# P0_Main_Connect.net
KiCad netlist of a schematic drawn in Altium Designer
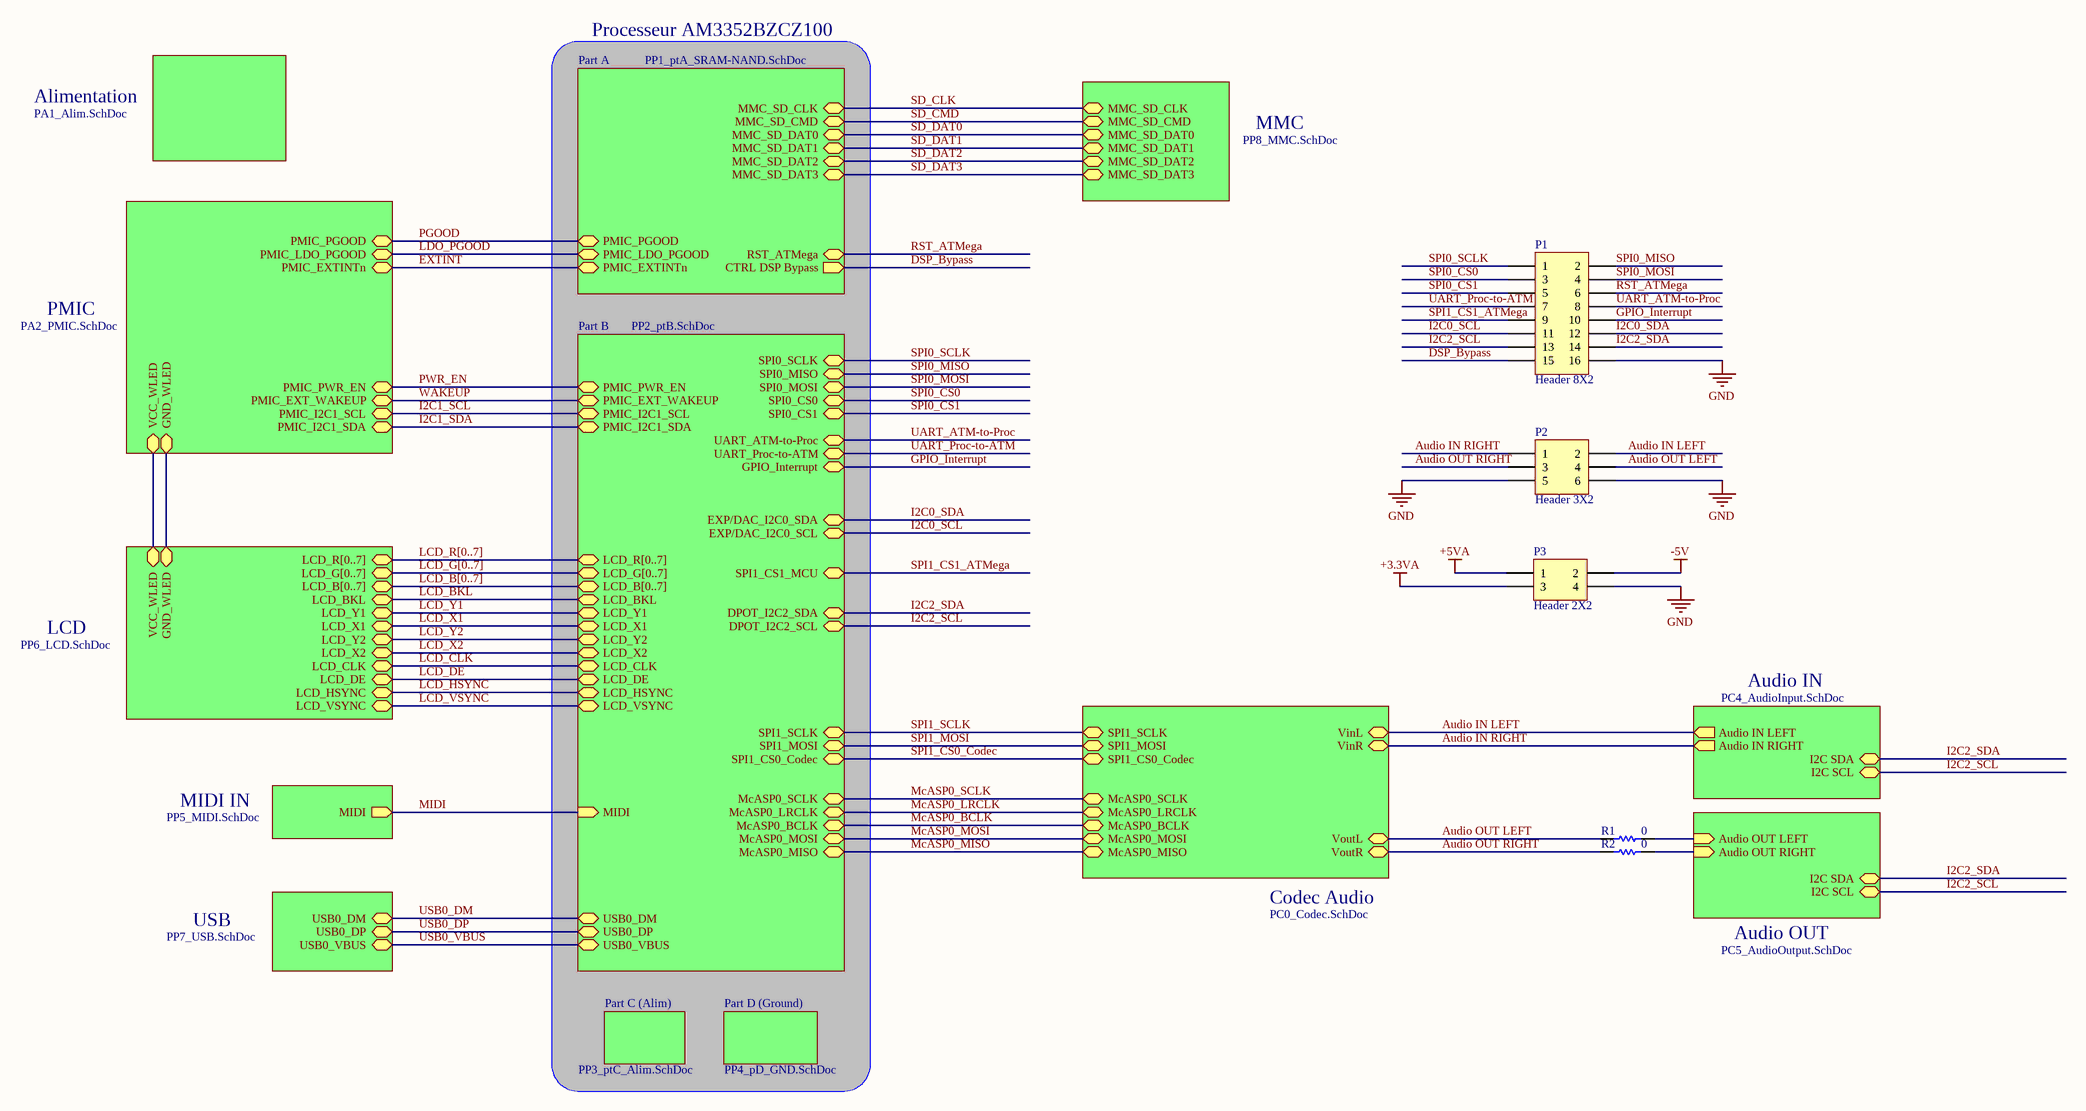
[diagram p0: P0_Main_Connect.SchDoc]

(export (version "E")
  (design (tool "Eeschema 10.0.6"))
  (components
    (comp (ref "P1")
      (value "Header 8X2")
      (footprint "CONN_1241050-8_T")
      (description "Header, 8-Pin, Dual row")
      (libsource (lib "Michel") (part "Header 8X2"))
    )
    (comp (ref "P2")
      (value "Header 3X2")
      (footprint "CONN_1241050-3_T")
      (description "Header, 3-Pin, Dual row")
      (libsource (lib "Michel") (part "Header 3X2"))
    )
    (comp (ref "P3")
      (value "Header 2X2")
      (footprint "CONN_1241050-2_T")
      (description "Header, 2-Pin, Dual row")
      (libsource (lib "Michel") (part "Header 2X2"))
    )
    (comp (ref "R1")
      (value "0")
      (footprint "RESC1608X05")
      (description "Resistor")
      (fields (field (name "Comment") "Res 0 Ohm"))
      (libsource (lib "Michel") (part "Res1"))
    )
    (comp (ref "R2")
      (value "0")
      (footprint "RESC1608X05")
      (description "Resistor")
      (fields (field (name "Comment") "Res 0 Ohm"))
      (libsource (lib "Michel") (part "Res1"))
    )
  )
  (nets
    (net (code "25") (name "+3.3VA") (class "Default")
      (node (ref "P3") (pin "3") (pinfunction "3_3") (pintype "passive"))
    )
    (net (code "26") (name "+5VA") (class "Default")
      (node (ref "P3") (pin "1") (pinfunction "1_1") (pintype "passive"))
    )
    (net (code "27") (name "-5V") (class "Default")
      (node (ref "P3") (pin "2") (pinfunction "2_2") (pintype "passive"))
    )
    (net (code "28") (name "/Audio IN LEFT") (class "Default")
      (node (ref "P2") (pin "2") (pinfunction "2_2") (pintype "passive"))
    )
    (net (code "29") (name "/Audio IN RIGHT") (class "Default")
      (node (ref "P2") (pin "1") (pinfunction "1_1") (pintype "passive"))
    )
    (net (code "30") (name "/Audio OUT LEFT") (class "Default")
      (node (ref "P2") (pin "4") (pinfunction "4_4") (pintype "passive"))
      (node (ref "R1") (pin "1") (pinfunction "1_1") (pintype "passive"))
    )
    (net (code "31") (name "/Audio OUT LEFT_1") (class "Default")
      (node (ref "R1") (pin "2") (pinfunction "2_2") (pintype "passive"))
    )
    (net (code "32") (name "/Audio OUT RIGHT") (class "Default")
      (node (ref "P2") (pin "3") (pinfunction "3_3") (pintype "passive"))
      (node (ref "R2") (pin "1") (pinfunction "1_1") (pintype "passive"))
    )
    (net (code "33") (name "/Audio OUT RIGHT_1") (class "Default")
      (node (ref "R2") (pin "2") (pinfunction "2_2") (pintype "passive"))
    )
    (net (code "34") (name "/DSP_Bypass") (class "Default")
      (node (ref "P1") (pin "15") (pinfunction "15_15") (pintype "passive"))
    )
    (net (code "37") (name "/GPIO_Interrupt") (class "Default")
      (node (ref "P1") (pin "10") (pinfunction "10_10") (pintype "passive"))
    )
    (net (code "38") (name "/I2C0_SCL") (class "Default")
      (node (ref "P1") (pin "11") (pinfunction "11_11") (pintype "passive"))
    )
    (net (code "39") (name "/I2C0_SDA") (class "Default")
      (node (ref "P1") (pin "12") (pinfunction "12_12") (pintype "passive"))
    )
    (net (code "42") (name "/I2C2_SCL") (class "Default")
      (node (ref "P1") (pin "13") (pinfunction "13_13") (pintype "passive"))
    )
    (net (code "43") (name "/I2C2_SDA") (class "Default")
      (node (ref "P1") (pin "14") (pinfunction "14_14") (pintype "passive"))
    )
    (net (code "65") (name "/RST_ATMega") (class "Default")
      (node (ref "P1") (pin "6") (pinfunction "6_6") (pintype "passive"))
    )
    (net (code "72") (name "/SPI0_CS0") (class "Default")
      (node (ref "P1") (pin "3") (pinfunction "3_3") (pintype "passive"))
    )
    (net (code "73") (name "/SPI0_CS1") (class "Default")
      (node (ref "P1") (pin "5") (pinfunction "5_5") (pintype "passive"))
    )
    (net (code "74") (name "/SPI0_MISO") (class "Default")
      (node (ref "P1") (pin "2") (pinfunction "2_2") (pintype "passive"))
    )
    (net (code "75") (name "/SPI0_MOSI") (class "Default")
      (node (ref "P1") (pin "4") (pinfunction "4_4") (pintype "passive"))
    )
    (net (code "76") (name "/SPI0_SCLK") (class "Default")
      (node (ref "P1") (pin "1") (pinfunction "1_1") (pintype "passive"))
    )
    (net (code "78") (name "/SPI1_CS1_ATMega") (class "Default")
      (node (ref "P1") (pin "9") (pinfunction "9_9") (pintype "passive"))
    )
    (net (code "81") (name "/UART_ATM-to-Proc") (class "Default")
      (node (ref "P1") (pin "8") (pinfunction "8_8") (pintype "passive"))
    )
    (net (code "82") (name "/UART_Proc-to-ATM") (class "Default")
      (node (ref "P1") (pin "7") (pinfunction "7_7") (pintype "passive"))
    )
    (net (code "88") (name "GND") (class "Default")
      (node (ref "P1") (pin "16") (pinfunction "16_16") (pintype "passive"))
      (node (ref "P2") (pin "5") (pinfunction "5_5") (pintype "passive"))
      (node (ref "P2") (pin "6") (pinfunction "6_6") (pintype "passive"))
      (node (ref "P3") (pin "4") (pinfunction "4_4") (pintype "passive"))
    )
  )
)
